# s3-pilot3.net
KiCad netlist of a schematic drawn in EAGLE
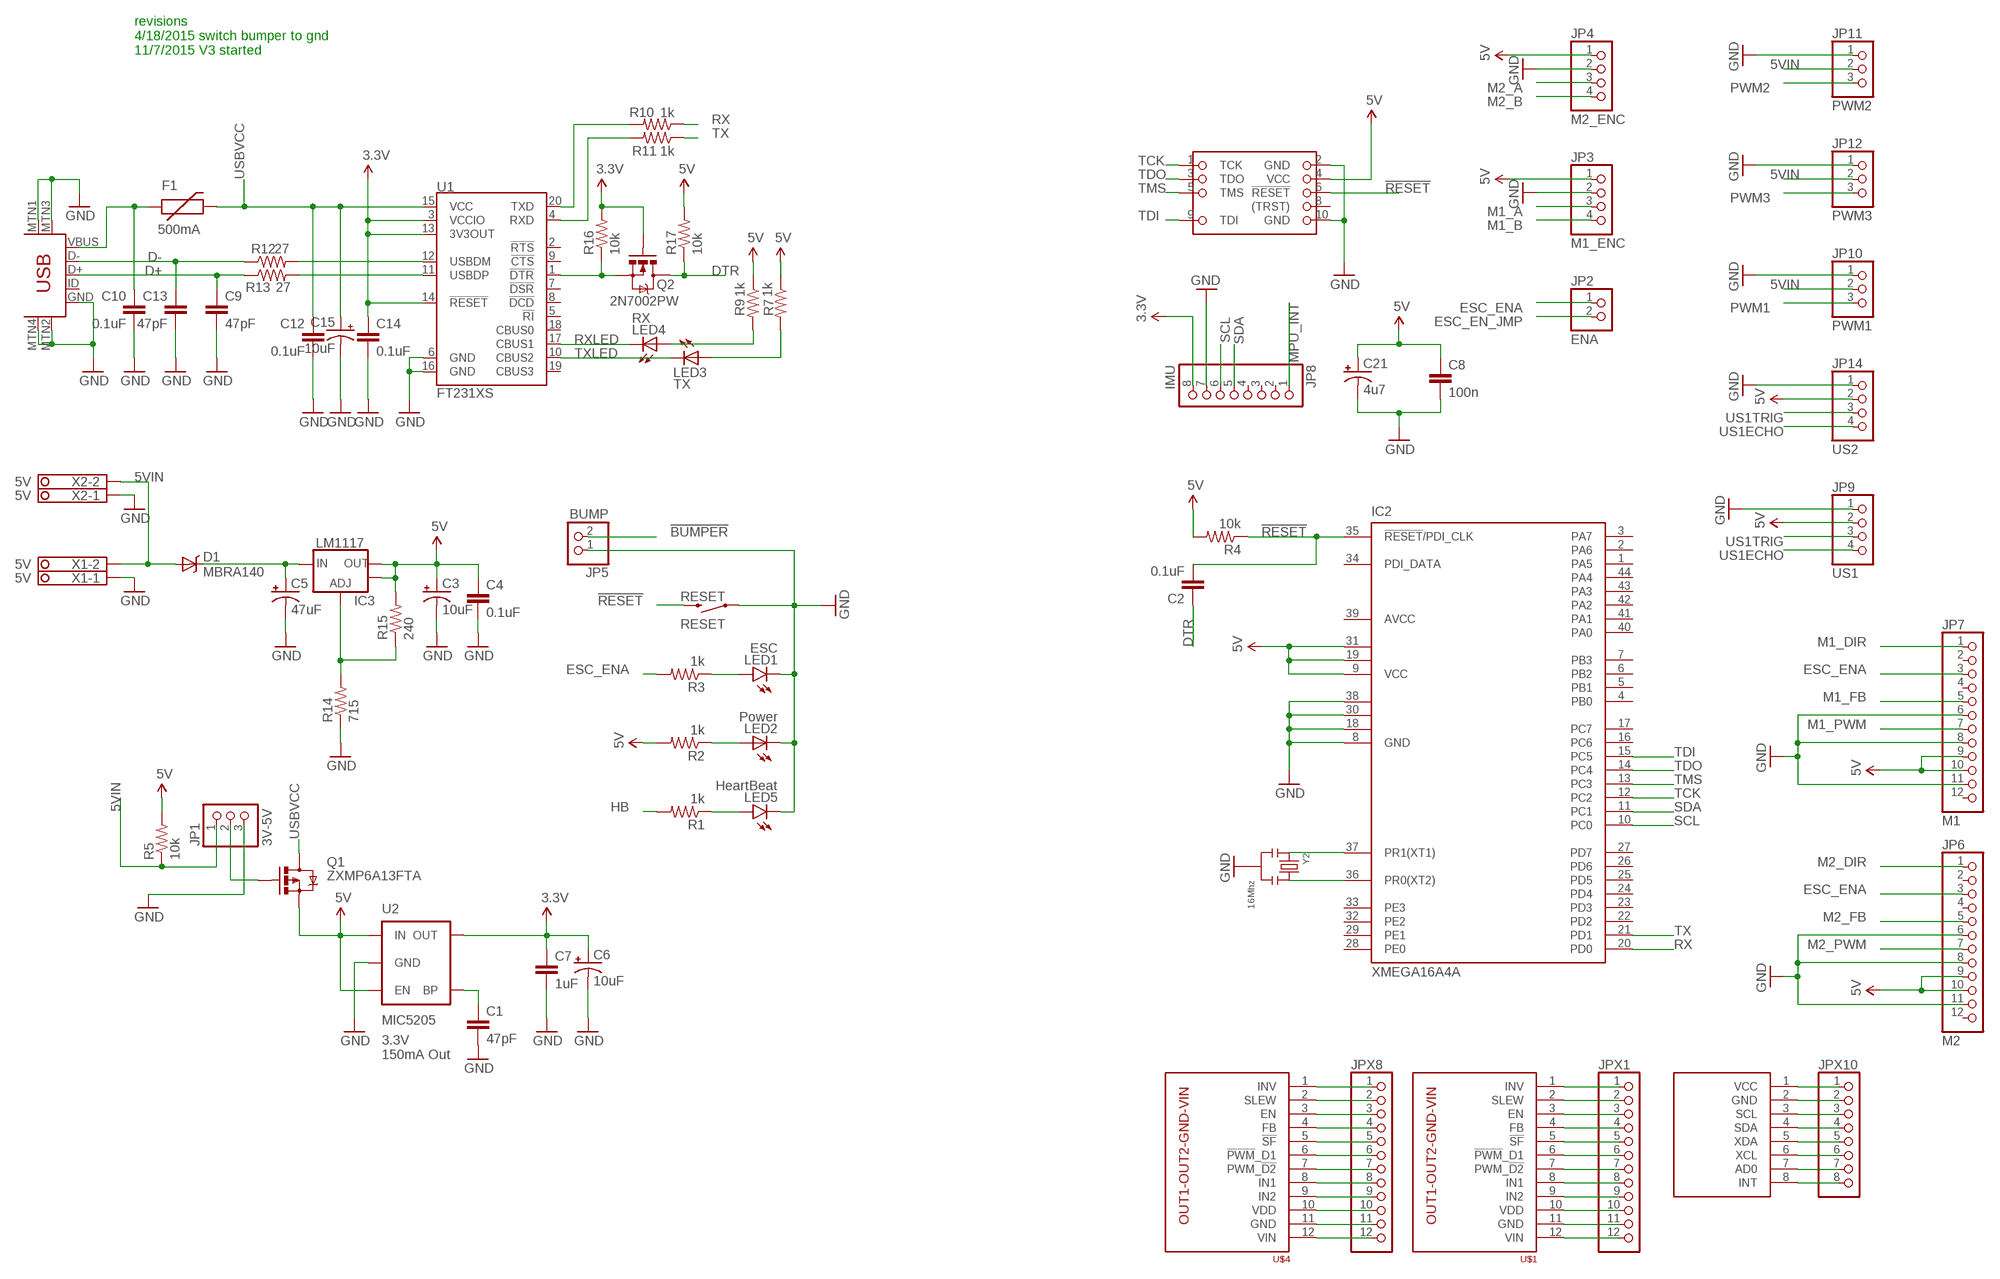
[diagram p0: schematic, sheet 1]

(export (version "E")
  (design (tool "Eeschema 10.0.6"))
  (components
    (comp (ref "C1")
      (value "47pF")
      (footprint "eagle-import:0603-CAP")
      (libsource (lib "eagle-import") (part "47PF-50V-5%(0603)"))
    )
    (comp (ref "C2")
      (value "0.1uF")
      (footprint "eagle-import:0805")
      (libsource (lib "eagle-import") (part "CAP0805"))
    )
    (comp (ref "C3")
      (value "10uF")
      (footprint "eagle-import:EIA3216")
      (libsource (lib "eagle-import") (part "CAP_POL1206"))
    )
    (comp (ref "C4")
      (value "0.1uF")
      (footprint "eagle-import:0603-CAP")
      (libsource (lib "eagle-import") (part "CAP0603-CAP"))
    )
    (comp (ref "C5")
      (value "47uF")
      (footprint "eagle-import:PANASONIC_D")
      (libsource (lib "eagle-import") (part "CAP_POLD"))
    )
    (comp (ref "C6")
      (value "10uF")
      (footprint "eagle-import:EIA3216")
      (libsource (lib "eagle-import") (part "CAP_POL1206"))
    )
    (comp (ref "C7")
      (value "1uF")
      (footprint "eagle-import:0603-CAP")
      (libsource (lib "eagle-import") (part "CAP0603-CAP"))
    )
    (comp (ref "C8")
      (value "100n")
      (footprint "eagle-import:0603-CAP")
      (libsource (lib "eagle-import") (part "CAP0603-CAP"))
    )
    (comp (ref "C9")
      (value "47pF")
      (footprint "eagle-import:0603-CAP")
      (libsource (lib "eagle-import") (part "47PF-50V-5%(0603)"))
    )
    (comp (ref "C10")
      (value "0.1uF")
      (footprint "eagle-import:0603-CAP")
      (libsource (lib "eagle-import") (part "CAP0603-CAP"))
    )
    (comp (ref "C12")
      (value "0.1uF")
      (footprint "eagle-import:0603-CAP")
      (libsource (lib "eagle-import") (part "CAP0603-CAP"))
    )
    (comp (ref "C13")
      (value "47pF")
      (footprint "eagle-import:0603-CAP")
      (libsource (lib "eagle-import") (part "47PF-50V-5%(0603)"))
    )
    (comp (ref "C14")
      (value "0.1uF")
      (footprint "eagle-import:0603-CAP")
      (libsource (lib "eagle-import") (part "CAP0603-CAP"))
    )
    (comp (ref "C15")
      (value "10uF")
      (footprint "eagle-import:EIA3216")
      (libsource (lib "eagle-import") (part "SparkFun-Capacitors_CAP_POL1206"))
    )
    (comp (ref "C21")
      (value "4u7")
      (footprint "eagle-import:EIA3216")
      (libsource (lib "eagle-import") (part "CAP_POL1206"))
    )
    (comp (ref "D1")
      (value "MBRA140")
      (footprint "eagle-import:SMA-DIODE")
      (libsource (lib "eagle-import") (part "DIODE-SCHOTTKY_"))
    )
    (comp (ref "F1")
      (value "500mA")
      (footprint "eagle-import:PTC-1206")
      (libsource (lib "eagle-import") (part "PTCSMD"))
    )
    (comp (ref "IC2")
      (value "XMEGA16A4A")
      (footprint "eagle-import:TQFP44")
      (libsource (lib "eagle-import") (part "XMEGA16A4A"))
    )
    (comp (ref "IC3")
      (value "LM1117")
      (footprint "eagle-import:SOT223")
      (libsource (lib "eagle-import") (part "V_REG_LM1117SOT223"))
    )
    (comp (ref "JP1")
      (value "3V-5V")
      (footprint "eagle-import:1X03")
      (libsource (lib "eagle-import") (part "PINHD-1X3"))
    )
    (comp (ref "JP2")
      (value "ENA")
      (footprint "eagle-import:1X02")
      (libsource (lib "eagle-import") (part "PINHD-1X2"))
    )
    (comp (ref "JP3")
      (value "M1_ENC")
      (footprint "eagle-import:1X04_90")
      (libsource (lib "eagle-import") (part "PINHD-1X4/90"))
    )
    (comp (ref "JP4")
      (value "M2_ENC")
      (footprint "eagle-import:1X04_90")
      (libsource (lib "eagle-import") (part "PINHD-1X4/90"))
    )
    (comp (ref "JP5")
      (value "BUMP")
      (footprint "eagle-import:1X02_90")
      (libsource (lib "eagle-import") (part "PINHD-1X2/90"))
    )
    (comp (ref "JP6")
      (value "M2")
      (footprint "eagle-import:1X12")
      (libsource (lib "eagle-import") (part "PINHD-1X12"))
    )
    (comp (ref "JP7")
      (value "M1")
      (footprint "eagle-import:1X12")
      (libsource (lib "eagle-import") (part "PINHD-1X12"))
    )
    (comp (ref "JP8")
      (value "IMU")
      (footprint "eagle-import:1X08")
      (libsource (lib "eagle-import") (part "PINHD-1X8"))
    )
    (comp (ref "JP9")
      (value "US1")
      (footprint "eagle-import:1X04_90")
      (libsource (lib "eagle-import") (part "PINHD-1X4/90"))
    )
    (comp (ref "JP10")
      (value "PWM1")
      (footprint "eagle-import:1X03_90")
      (libsource (lib "eagle-import") (part "PINHD-1X3/90"))
    )
    (comp (ref "JP11")
      (value "PWM2")
      (footprint "eagle-import:1X03_90")
      (libsource (lib "eagle-import") (part "PINHD-1X3/90"))
    )
    (comp (ref "JP12")
      (value "PWM3")
      (footprint "eagle-import:1X03_90")
      (libsource (lib "eagle-import") (part "PINHD-1X3/90"))
    )
    (comp (ref "JP14")
      (value "US2")
      (footprint "eagle-import:1X04_90")
      (libsource (lib "eagle-import") (part "PINHD-1X4/90"))
    )
    (comp (ref "JPX1")
      (value "PINHD-1X12")
      (footprint "eagle-import:1X12")
      (libsource (lib "eagle-import") (part "PINHD-1X12"))
    )
    (comp (ref "JPX8")
      (value "PINHD-1X12")
      (footprint "eagle-import:1X12")
      (libsource (lib "eagle-import") (part "PINHD-1X12"))
    )
    (comp (ref "JPX10")
      (value "PINHD-1X8")
      (footprint "eagle-import:1X08")
      (libsource (lib "eagle-import") (part "PINHD-1X8"))
    )
    (comp (ref "LED1")
      (value "ESC")
      (footprint "eagle-import:LED-1206")
      (libsource (lib "eagle-import") (part "LED-RED1206"))
    )
    (comp (ref "LED2")
      (value "Power")
      (footprint "eagle-import:LED-1206")
      (libsource (lib "eagle-import") (part "LED1206"))
    )
    (comp (ref "LED3")
      (value "TX")
      (footprint "eagle-import:LED-1206")
      (libsource (lib "eagle-import") (part "LED1206"))
    )
    (comp (ref "LED4")
      (value "RX")
      (footprint "eagle-import:LED-1206")
      (libsource (lib "eagle-import") (part "LED1206"))
    )
    (comp (ref "LED5")
      (value "HeartBeat")
      (footprint "eagle-import:LED-1206")
      (libsource (lib "eagle-import") (part "LED-RED1206"))
    )
    (comp (ref "MPU6050")
      (value "MPU-6050-BO")
      (footprint "eagle-import:MPU-6050-BO")
      (libsource (lib "eagle-import") (part "MPU-6050-BO"))
    )
    (comp (ref "Q1")
      (value "ZXMP6A13FTA")
      (footprint "eagle-import:SOT23-3")
      (libsource (lib "eagle-import") (part "MOSFET-PCHANNELSMD"))
    )
    (comp (ref "Q2")
      (value "2N7002PW")
      (footprint "eagle-import:SOT323")
      (libsource (lib "eagle-import") (part "MOSFET-NCHANNEL2N7002PW"))
    )
    (comp (ref "R1")
      (value "1k")
      (footprint "eagle-import:0603-RES")
      (libsource (lib "eagle-import") (part "RESISTOR0603-RES"))
    )
    (comp (ref "R2")
      (value "1k")
      (footprint "eagle-import:0603-RES")
      (libsource (lib "eagle-import") (part "RESISTOR0603-RES"))
    )
    (comp (ref "R3")
      (value "1k")
      (footprint "eagle-import:0603-RES")
      (libsource (lib "eagle-import") (part "RESISTOR0603-RES"))
    )
    (comp (ref "R4")
      (value "10k")
      (footprint "eagle-import:0603-RES")
      (libsource (lib "eagle-import") (part "RESISTOR0603-RES"))
    )
    (comp (ref "R5")
      (value "10k")
      (footprint "eagle-import:0603-RES")
      (libsource (lib "eagle-import") (part "RESISTOR0603-RES"))
    )
    (comp (ref "R7")
      (value "1k")
      (footprint "eagle-import:0603-RES")
      (libsource (lib "eagle-import") (part "RESISTOR0603-RES"))
    )
    (comp (ref "R9")
      (value "1k")
      (footprint "eagle-import:0603-RES")
      (libsource (lib "eagle-import") (part "RESISTOR0603-RES"))
    )
    (comp (ref "R10")
      (value "1k")
      (footprint "eagle-import:0603-RES")
      (libsource (lib "eagle-import") (part "RESISTOR0603-RES"))
    )
    (comp (ref "R11")
      (value "1k")
      (footprint "eagle-import:0603-RES")
      (libsource (lib "eagle-import") (part "RESISTOR0603-RES"))
    )
    (comp (ref "R12")
      (value "27")
      (footprint "eagle-import:0603-RES")
      (libsource (lib "eagle-import") (part "SparkFun-Resistors_RESISTOR0603-RES"))
    )
    (comp (ref "R13")
      (value "27")
      (footprint "eagle-import:0603-RES")
      (libsource (lib "eagle-import") (part "SparkFun-Resistors_RESISTOR0603-RES"))
    )
    (comp (ref "R14")
      (value "715")
      (footprint "eagle-import:0603-RES")
      (libsource (lib "eagle-import") (part "RESISTOR0603-RES"))
    )
    (comp (ref "R15")
      (value "240")
      (footprint "eagle-import:0603-RES")
      (libsource (lib "eagle-import") (part "RESISTOR0603-RES"))
    )
    (comp (ref "R16")
      (value "10k")
      (footprint "eagle-import:0603-RES")
      (libsource (lib "eagle-import") (part "RESISTOR0603-RES"))
    )
    (comp (ref "R17")
      (value "10k")
      (footprint "eagle-import:0603-RES")
      (libsource (lib "eagle-import") (part "RESISTOR0603-RES"))
    )
    (comp (ref "RESET")
      (value "RESET")
      (footprint "eagle-import:TACTILE_SWITCH_TALL")
      (libsource (lib "eagle-import") (part "SWITCH-MOMENTARY-2SMD-4"))
    )
    (comp (ref "U$1")
      (value "M2")
      (footprint "eagle-import:MC33926-SINGLE-BO")
      (libsource (lib "eagle-import") (part "MC33926-SINGLE-BO"))
    )
    (comp (ref "U$2")
      (value "JTAG")
      (footprint "eagle-import:2X5_05")
      (libsource (lib "eagle-import") (part "CON-JTAG"))
    )
    (comp (ref "U$4")
      (value "M2")
      (footprint "eagle-import:MC33926-SINGLE-BO")
      (libsource (lib "eagle-import") (part "MC33926-SINGLE-BO"))
    )
    (comp (ref "U$13")
      (value "USB-MINIB-5PIN")
      (footprint "eagle-import:USB-MINIB")
      (libsource (lib "eagle-import") (part "USB-MINIB-5PIN"))
    )
    (comp (ref "U1")
      (value "FT231XS")
      (footprint "eagle-import:SSOP20_L")
      (libsource (lib "eagle-import") (part "FT231XS"))
    )
    (comp (ref "U2")
      (value "MIC5205")
      (footprint "eagle-import:SOT23-5")
      (libsource (lib "eagle-import") (part "V_REG_LDOSMD"))
    )
    (comp (ref "X1")
      (value "5V")
      (footprint "eagle-import:1751248")
      (libsource (lib "eagle-import") (part "1751248"))
    )
    (comp (ref "X2")
      (value "5V")
      (footprint "eagle-import:1751248")
      (libsource (lib "eagle-import") (part "1751248"))
    )
    (comp (ref "Y2")
      (value "16Mhz")
      (footprint "eagle-import:SMD-KYOCERA-PBRV-H")
      (libsource (lib "eagle-import") (part "SMD-RESONATOR-KYOCERA-PBRV-H"))
    )
  )
  (nets
    (net (code "1") (name "/5VIN") (class "Default")
      (node (ref "D1") (pin "A") (pinfunction "A_A") (pintype "passive"))
      (node (ref "JP1") (pin "1") (pinfunction "1_1") (pintype "passive"))
      (node (ref "JP10") (pin "2") (pinfunction "2_2") (pintype "passive"))
      (node (ref "JP11") (pin "2") (pinfunction "2_2") (pintype "passive"))
      (node (ref "JP12") (pin "2") (pinfunction "2_2") (pintype "passive"))
      (node (ref "R5") (pin "1") (pinfunction "1_1") (pintype "passive"))
      (node (ref "X1") (pin "2") (pinfunction "K_2") (pintype "passive"))
      (node (ref "X2") (pin "2") (pinfunction "K_2") (pintype "passive"))
    )
    (net (code "2") (name "/AVCC") (class "Default")
      (node (ref "IC2") (pin "39") (pinfunction "AVCC_39") (pintype "power_in"))
    )
    (net (code "3") (name "/D+") (class "Default")
      (node (ref "C9") (pin "1") (pinfunction "1_1") (pintype "passive"))
      (node (ref "R13") (pin "1") (pinfunction "1_1") (pintype "passive"))
      (node (ref "U$13") (pin "D+") (pinfunction "D+_D+") (pintype "bidirectional"))
    )
    (net (code "4") (name "/D-") (class "Default")
      (node (ref "C13") (pin "1") (pinfunction "1_1") (pintype "passive"))
      (node (ref "R12") (pin "1") (pinfunction "1_1") (pintype "passive"))
      (node (ref "U$13") (pin "D-") (pinfunction "D-_D-") (pintype "bidirectional"))
    )
    (net (code "5") (name "/DTR") (class "Default")
      (node (ref "C2") (pin "1") (pinfunction "1_1") (pintype "passive"))
      (node (ref "Q2") (pin "3") (pinfunction "D_3") (pintype "passive"))
      (node (ref "R17") (pin "1") (pinfunction "1_1") (pintype "passive"))
    )
    (net (code "6") (name "/ESC_ENA") (class "Default")
      (node (ref "JP2") (pin "1") (pinfunction "1_1") (pintype "passive"))
      (node (ref "JP6") (pin "3") (pinfunction "3_3") (pintype "passive"))
      (node (ref "JP7") (pin "3") (pinfunction "3_3") (pintype "passive"))
      (node (ref "R3") (pin "2") (pinfunction "2_2") (pintype "passive"))
    )
    (net (code "7") (name "/ESC_EN_JMP") (class "Default")
      (node (ref "JP2") (pin "2") (pinfunction "2_2") (pintype "passive"))
    )
    (net (code "8") (name "/HB") (class "Default")
      (node (ref "R1") (pin "2") (pinfunction "2_2") (pintype "passive"))
    )
    (net (code "9") (name "/M1_A") (class "Default")
      (node (ref "JP3") (pin "3") (pinfunction "3_3") (pintype "passive"))
    )
    (net (code "10") (name "/M1_B") (class "Default")
      (node (ref "JP3") (pin "4") (pinfunction "4_4") (pintype "passive"))
    )
    (net (code "11") (name "/M1_DIR") (class "Default")
      (node (ref "JP7") (pin "1") (pinfunction "1_1") (pintype "passive"))
    )
    (net (code "12") (name "/M1_FB") (class "Default")
      (node (ref "JP7") (pin "5") (pinfunction "5_5") (pintype "passive"))
    )
    (net (code "13") (name "/M1_PWM") (class "Default")
      (node (ref "JP7") (pin "7") (pinfunction "7_7") (pintype "passive"))
    )
    (net (code "14") (name "/M2_A") (class "Default")
      (node (ref "JP4") (pin "3") (pinfunction "3_3") (pintype "passive"))
    )
    (net (code "15") (name "/M2_B") (class "Default")
      (node (ref "JP4") (pin "4") (pinfunction "4_4") (pintype "passive"))
    )
    (net (code "16") (name "/M2_DIR") (class "Default")
      (node (ref "JP6") (pin "1") (pinfunction "1_1") (pintype "passive"))
    )
    (net (code "17") (name "/M2_FB") (class "Default")
      (node (ref "JP6") (pin "5") (pinfunction "5_5") (pintype "passive"))
    )
    (net (code "18") (name "/M2_PWM") (class "Default")
      (node (ref "JP6") (pin "7") (pinfunction "7_7") (pintype "passive"))
    )
    (net (code "19") (name "/MPU_INT") (class "Default")
      (node (ref "JP8") (pin "1") (pinfunction "1_1") (pintype "passive"))
    )
    (net (code "20") (name "/PWM1") (class "Default")
      (node (ref "JP10") (pin "3") (pinfunction "3_3") (pintype "passive"))
    )
    (net (code "21") (name "/PWM2") (class "Default")
      (node (ref "JP11") (pin "3") (pinfunction "3_3") (pintype "passive"))
    )
    (net (code "22") (name "/PWM3") (class "Default")
      (node (ref "JP12") (pin "3") (pinfunction "3_3") (pintype "passive"))
    )
    (net (code "23") (name "/RX") (class "Default")
      (node (ref "IC2") (pin "20") (pinfunction "PD0_20") (pintype "bidirectional"))
      (node (ref "R10") (pin "1") (pinfunction "1_1") (pintype "passive"))
    )
    (net (code "24") (name "/RXLED") (class "Default")
      (node (ref "LED4") (pin "C") (pinfunction "C_C") (pintype "passive"))
      (node (ref "U1") (pin "17") (pinfunction "CBUS1_17") (pintype "bidirectional"))
    )
    (net (code "25") (name "/SCL") (class "Default")
      (node (ref "IC2") (pin "10") (pinfunction "PC0_10") (pintype "bidirectional"))
      (node (ref "JP8") (pin "6") (pinfunction "6_6") (pintype "passive"))
    )
    (net (code "26") (name "/SDA") (class "Default")
      (node (ref "IC2") (pin "11") (pinfunction "PC1_11") (pintype "bidirectional"))
      (node (ref "JP8") (pin "5") (pinfunction "5_5") (pintype "passive"))
    )
    (net (code "27") (name "/TCK") (class "Default")
      (node (ref "IC2") (pin "12") (pinfunction "PC2_12") (pintype "bidirectional"))
      (node (ref "U$2") (pin "1") (pinfunction "TCK_1") (pintype "bidirectional"))
    )
    (net (code "28") (name "/TDI") (class "Default")
      (node (ref "IC2") (pin "15") (pinfunction "PC5_15") (pintype "bidirectional"))
      (node (ref "U$2") (pin "9") (pinfunction "TDI_9") (pintype "bidirectional"))
    )
    (net (code "29") (name "/TDO") (class "Default")
      (node (ref "IC2") (pin "14") (pinfunction "PC4_14") (pintype "bidirectional"))
      (node (ref "U$2") (pin "3") (pinfunction "TDO_3") (pintype "bidirectional"))
    )
    (net (code "30") (name "/TMS") (class "Default")
      (node (ref "IC2") (pin "13") (pinfunction "PC3_13") (pintype "bidirectional"))
      (node (ref "U$2") (pin "5") (pinfunction "TMS_5") (pintype "bidirectional"))
    )
    (net (code "31") (name "/TX") (class "Default")
      (node (ref "IC2") (pin "21") (pinfunction "PD1_21") (pintype "bidirectional"))
      (node (ref "R11") (pin "1") (pinfunction "1_1") (pintype "passive"))
    )
    (net (code "32") (name "/TXLED") (class "Default")
      (node (ref "LED3") (pin "C") (pinfunction "C_C") (pintype "passive"))
      (node (ref "U1") (pin "10") (pinfunction "CBUS2_10") (pintype "bidirectional"))
    )
    (net (code "33") (name "/US1ECHO") (class "Default")
      (node (ref "JP14") (pin "4") (pinfunction "4_4") (pintype "passive"))
      (node (ref "JP9") (pin "4") (pinfunction "4_4") (pintype "passive"))
    )
    (net (code "34") (name "/US1TRIG") (class "Default")
      (node (ref "JP14") (pin "3") (pinfunction "3_3") (pintype "passive"))
      (node (ref "JP9") (pin "3") (pinfunction "3_3") (pintype "passive"))
    )
    (net (code "35") (name "/USBVCC") (class "Default")
      (node (ref "C12") (pin "1") (pinfunction "1_1") (pintype "passive"))
      (node (ref "C15") (pin "A") (pinfunction "+_A") (pintype "passive"))
      (node (ref "F1") (pin "2") (pinfunction "2_2") (pintype "bidirectional"))
      (node (ref "Q1") (pin "3") (pinfunction "D_3") (pintype "passive"))
      (node (ref "U1") (pin "15") (pinfunction "VCC_15") (pintype "bidirectional"))
    )
    (net (code "36") (name "/~{BUMPER}") (class "Default")
      (node (ref "JP5") (pin "2") (pinfunction "2_2") (pintype "passive"))
    )
    (net (code "37") (name "/~{RESET}") (class "Default")
      (node (ref "C2") (pin "2") (pinfunction "2_2") (pintype "passive"))
      (node (ref "IC2") (pin "35") (pinfunction "~{RESET}/PDI_CLK_35") (pintype "bidirectional"))
      (node (ref "R4") (pin "1") (pinfunction "1_1") (pintype "passive"))
      (node (ref "RESET") (pin "B2") (pinfunction "2_B2") (pintype "passive"))
      (node (ref "U$2") (pin "6") (pinfunction "~{RESET}_6") (pintype "bidirectional"))
    )
    (net (code "38") (name "3.3V") (class "Default")
      (node (ref "C14") (pin "1") (pinfunction "1_1") (pintype "passive"))
      (node (ref "C6") (pin "A") (pinfunction "+_A") (pintype "passive"))
      (node (ref "C7") (pin "1") (pinfunction "1_1") (pintype "passive"))
      (node (ref "JP8") (pin "8") (pinfunction "8_8") (pintype "passive"))
      (node (ref "Q2") (pin "1") (pinfunction "G_1") (pintype "passive"))
      (node (ref "R16") (pin "2") (pinfunction "2_2") (pintype "passive"))
      (node (ref "U1") (pin "13") (pinfunction "3V3OUT_13") (pintype "bidirectional"))
      (node (ref "U1") (pin "14") (pinfunction "~{RESET}_14") (pintype "bidirectional"))
      (node (ref "U1") (pin "3") (pinfunction "VCCIO_3") (pintype "bidirectional"))
      (node (ref "U2") (pin "5") (pinfunction "OUT_5") (pintype "passive"))
    )
    (net (code "39") (name "5V") (class "Default")
      (node (ref "C21") (pin "A") (pinfunction "+_A") (pintype "passive"))
      (node (ref "C3") (pin "A") (pinfunction "+_A") (pintype "passive"))
      (node (ref "C4") (pin "1") (pinfunction "1_1") (pintype "passive"))
      (node (ref "C8") (pin "1") (pinfunction "1_1") (pintype "passive"))
      (node (ref "IC2") (pin "19") (pinfunction "VCC1_19") (pintype "power_in"))
      (node (ref "IC2") (pin "31") (pinfunction "VCC2_31") (pintype "power_in"))
      (node (ref "IC2") (pin "9") (pinfunction "VCC_9") (pintype "power_in"))
      (node (ref "IC3") (pin "2") (pinfunction "OUT_2") (pintype "output"))
      (node (ref "IC3") (pin "4") (pinfunction "OUT_4") (pintype "output"))
      (node (ref "JP14") (pin "2") (pinfunction "2_2") (pintype "passive"))
      (node (ref "JP3") (pin "1") (pinfunction "1_1") (pintype "passive"))
      (node (ref "JP4") (pin "1") (pinfunction "1_1") (pintype "passive"))
      (node (ref "JP6") (pin "10") (pinfunction "10_10") (pintype "passive"))
      (node (ref "JP6") (pin "9") (pinfunction "9_9") (pintype "passive"))
      (node (ref "JP7") (pin "10") (pinfunction "10_10") (pintype "passive"))
      (node (ref "JP7") (pin "9") (pinfunction "9_9") (pintype "passive"))
      (node (ref "JP9") (pin "2") (pinfunction "2_2") (pintype "passive"))
      (node (ref "Q1") (pin "2") (pinfunction "S_2") (pintype "passive"))
      (node (ref "R15") (pin "2") (pinfunction "2_2") (pintype "passive"))
      (node (ref "R17") (pin "2") (pinfunction "2_2") (pintype "passive"))
      (node (ref "R2") (pin "2") (pinfunction "2_2") (pintype "passive"))
      (node (ref "R4") (pin "2") (pinfunction "2_2") (pintype "passive"))
      (node (ref "R5") (pin "2") (pinfunction "2_2") (pintype "passive"))
      (node (ref "R7") (pin "1") (pinfunction "1_1") (pintype "passive"))
      (node (ref "R9") (pin "1") (pinfunction "1_1") (pintype "passive"))
      (node (ref "U$2") (pin "4") (pinfunction "VCC_4") (pintype "power_in"))
      (node (ref "U2") (pin "1") (pinfunction "IN_1") (pintype "input"))
      (node (ref "U2") (pin "3") (pinfunction "EN_3") (pintype "input"))
    )
    (net (code "40") (name "GND") (class "Default")
      (node (ref "C1") (pin "2") (pinfunction "2_2") (pintype "passive"))
      (node (ref "C10") (pin "2") (pinfunction "2_2") (pintype "passive"))
      (node (ref "C12") (pin "2") (pinfunction "2_2") (pintype "passive"))
      (node (ref "C13") (pin "2") (pinfunction "2_2") (pintype "passive"))
      (node (ref "C14") (pin "2") (pinfunction "2_2") (pintype "passive"))
      (node (ref "C15") (pin "C") (pinfunction "-_C") (pintype "passive"))
      (node (ref "C21") (pin "C") (pinfunction "-_C") (pintype "passive"))
      (node (ref "C3") (pin "C") (pinfunction "-_C") (pintype "passive"))
      (node (ref "C4") (pin "2") (pinfunction "2_2") (pintype "passive"))
      (node (ref "C5") (pin "-") (pinfunction "-_-") (pintype "passive"))
      (node (ref "C6") (pin "C") (pinfunction "-_C") (pintype "passive"))
      (node (ref "C7") (pin "2") (pinfunction "2_2") (pintype "passive"))
      (node (ref "C8") (pin "2") (pinfunction "2_2") (pintype "passive"))
      (node (ref "C9") (pin "2") (pinfunction "2_2") (pintype "passive"))
      (node (ref "IC2") (pin "18") (pinfunction "GND1_18") (pintype "power_in"))
      (node (ref "IC2") (pin "30") (pinfunction "GND2_30") (pintype "power_in"))
      (node (ref "IC2") (pin "38") (pinfunction "GND3_38") (pintype "power_in"))
      (node (ref "IC2") (pin "8") (pinfunction "GND_8") (pintype "power_in"))
      (node (ref "JP1") (pin "3") (pinfunction "3_3") (pintype "passive"))
      (node (ref "JP10") (pin "1") (pinfunction "1_1") (pintype "passive"))
      (node (ref "JP11") (pin "1") (pinfunction "1_1") (pintype "passive"))
      (node (ref "JP12") (pin "1") (pinfunction "1_1") (pintype "passive"))
      (node (ref "JP14") (pin "1") (pinfunction "1_1") (pintype "passive"))
      (node (ref "JP3") (pin "2") (pinfunction "2_2") (pintype "passive"))
      (node (ref "JP4") (pin "2") (pinfunction "2_2") (pintype "passive"))
      (node (ref "JP5") (pin "1") (pinfunction "1_1") (pintype "passive"))
      (node (ref "JP6") (pin "11") (pinfunction "11_11") (pintype "passive"))
      (node (ref "JP6") (pin "6") (pinfunction "6_6") (pintype "passive"))
      (node (ref "JP6") (pin "8") (pinfunction "8_8") (pintype "passive"))
      (node (ref "JP7") (pin "11") (pinfunction "11_11") (pintype "passive"))
      (node (ref "JP7") (pin "6") (pinfunction "6_6") (pintype "passive"))
      (node (ref "JP7") (pin "8") (pinfunction "8_8") (pintype "passive"))
      (node (ref "JP8") (pin "7") (pinfunction "7_7") (pintype "passive"))
      (node (ref "JP9") (pin "1") (pinfunction "1_1") (pintype "passive"))
      (node (ref "LED1") (pin "C") (pinfunction "C_C") (pintype "passive"))
      (node (ref "LED2") (pin "C") (pinfunction "C_C") (pintype "passive"))
      (node (ref "LED5") (pin "C") (pinfunction "C_C") (pintype "passive"))
      (node (ref "R14") (pin "1") (pinfunction "1_1") (pintype "passive"))
      (node (ref "RESET") (pin "A2") (pinfunction "1_A2") (pintype "passive"))
      (node (ref "U$13") (pin "GND") (pinfunction "GND_GND") (pintype "bidirectional"))
      (node (ref "U$13") (pin "MTN1") (pinfunction "MTN2_MTN1") (pintype "bidirectional"))
      (node (ref "U$13") (pin "MTN2") (pinfunction "MTN3_MTN2") (pintype "bidirectional"))
      (node (ref "U$13") (pin "MTN3") (pinfunction "MTN1_MTN3") (pintype "bidirectional"))
      (node (ref "U$13") (pin "MTN4") (pinfunction "MTN4_MTN4") (pintype "bidirectional"))
      (node (ref "U$2") (pin "10") (pinfunction "GND_10") (pintype "power_in"))
      (node (ref "U$2") (pin "2") (pinfunction "GND_2") (pintype "power_in"))
      (node (ref "U1") (pin "16") (pinfunction "GND_16") (pintype "bidirectional"))
      (node (ref "U1") (pin "6") (pinfunction "GND_6") (pintype "bidirectional"))
      (node (ref "U2") (pin "2") (pinfunction "GND_2") (pintype "input"))
      (node (ref "X1") (pin "1") (pinfunction "K_1") (pintype "passive"))
      (node (ref "X2") (pin "1") (pinfunction "K_1") (pintype "passive"))
      (node (ref "Y2") (pin "2") (pinfunction "2_2") (pintype "passive"))
    )
    (net (code "41") (name "Net-(C10-Pad1)") (class "Default")
      (node (ref "C10") (pin "1") (pinfunction "1_1") (pintype "passive"))
      (node (ref "F1") (pin "1") (pinfunction "1_1") (pintype "bidirectional"))
      (node (ref "U$13") (pin "VBUS") (pinfunction "VBUS_VBUS") (pintype "bidirectional"))
    )
    (net (code "42") (name "Net-(IC2-PR0(XT2))") (class "Default")
      (node (ref "IC2") (pin "36") (pinfunction "PR0(XT2)_36") (pintype "bidirectional"))
      (node (ref "Y2") (pin "3") (pinfunction "3_3") (pintype "passive"))
    )
    (net (code "43") (name "Net-(IC2-PR1(XT1))") (class "Default")
      (node (ref "IC2") (pin "37") (pinfunction "PR1(XT1)_37") (pintype "bidirectional"))
      (node (ref "Y2") (pin "1") (pinfunction "1_1") (pintype "passive"))
    )
    (net (code "44") (name "Net-(IC3-ADJ)") (class "Default")
      (node (ref "IC3") (pin "1") (pinfunction "ADJ_1") (pintype "input"))
      (node (ref "R14") (pin "2") (pinfunction "2_2") (pintype "passive"))
      (node (ref "R15") (pin "1") (pinfunction "1_1") (pintype "passive"))
    )
    (net (code "45") (name "Net-(IC3-IN)") (class "Default")
      (node (ref "C5") (pin "+") (pinfunction "+_+") (pintype "passive"))
      (node (ref "D1") (pin "C") (pinfunction "C_C") (pintype "passive"))
      (node (ref "IC3") (pin "3") (pinfunction "IN_3") (pintype "input"))
    )
    (net (code "46") (name "Net-(LED1-PadA)") (class "Default")
      (node (ref "LED1") (pin "A") (pinfunction "A_A") (pintype "passive"))
      (node (ref "R3") (pin "1") (pinfunction "1_1") (pintype "passive"))
    )
    (net (code "47") (name "Net-(LED2-PadA)") (class "Default")
      (node (ref "LED2") (pin "A") (pinfunction "A_A") (pintype "passive"))
      (node (ref "R2") (pin "1") (pinfunction "1_1") (pintype "passive"))
    )
    (net (code "48") (name "Net-(LED3-PadA)") (class "Default")
      (node (ref "LED3") (pin "A") (pinfunction "A_A") (pintype "passive"))
      (node (ref "R7") (pin "2") (pinfunction "2_2") (pintype "passive"))
    )
    (net (code "49") (name "Net-(LED4-PadA)") (class "Default")
      (node (ref "LED4") (pin "A") (pinfunction "A_A") (pintype "passive"))
      (node (ref "R9") (pin "2") (pinfunction "2_2") (pintype "passive"))
    )
    (net (code "50") (name "Net-(LED5-PadA)") (class "Default")
      (node (ref "LED5") (pin "A") (pinfunction "A_A") (pintype "passive"))
      (node (ref "R1") (pin "1") (pinfunction "1_1") (pintype "passive"))
    )
    (net (code "51") (name "Net-(MPU6050-AD0)") (class "Default")
      (node (ref "JPX10") (pin "7") (pinfunction "7_7") (pintype "passive"))
      (node (ref "MPU6050") (pin "7") (pinfunction "AD0_7") (pintype "input"))
    )
    (net (code "52") (name "Net-(MPU6050-GND)") (class "Default")
      (node (ref "JPX10") (pin "2") (pinfunction "2_2") (pintype "passive"))
      (node (ref "MPU6050") (pin "2") (pinfunction "GND_2") (pintype "power_in"))
    )
    (net (code "53") (name "Net-(MPU6050-INT)") (class "Default")
      (node (ref "JPX10") (pin "8") (pinfunction "8_8") (pintype "passive"))
      (node (ref "MPU6050") (pin "8") (pinfunction "INT_8") (pintype "output"))
    )
    (net (code "54") (name "Net-(MPU6050-SCL)") (class "Default")
      (node (ref "JPX10") (pin "3") (pinfunction "3_3") (pintype "passive"))
      (node (ref "MPU6050") (pin "3") (pinfunction "SCL_3") (pintype "bidirectional"))
    )
    (net (code "55") (name "Net-(MPU6050-SDA)") (class "Default")
      (node (ref "JPX10") (pin "4") (pinfunction "4_4") (pintype "passive"))
      (node (ref "MPU6050") (pin "4") (pinfunction "SDA_4") (pintype "bidirectional"))
    )
    (net (code "56") (name "Net-(MPU6050-VCC)") (class "Default")
      (node (ref "JPX10") (pin "1") (pinfunction "1_1") (pintype "passive"))
      (node (ref "MPU6050") (pin "1") (pinfunction "VCC_1") (pintype "power_in"))
    )
    (net (code "57") (name "Net-(MPU6050-XCL)") (class "Default")
      (node (ref "JPX10") (pin "6") (pinfunction "6_6") (pintype "passive"))
      (node (ref "MPU6050") (pin "6") (pinfunction "XCL_6") (pintype "bidirectional"))
    )
    (net (code "58") (name "Net-(MPU6050-XDA)") (class "Default")
      (node (ref "JPX10") (pin "5") (pinfunction "5_5") (pintype "passive"))
      (node (ref "MPU6050") (pin "5") (pinfunction "XDA_5") (pintype "bidirectional"))
    )
    (net (code "59") (name "Net-(Q1-G)") (class "Default")
      (node (ref "JP1") (pin "2") (pinfunction "2_2") (pintype "passive"))
      (node (ref "Q1") (pin "1") (pinfunction "G_1") (pintype "passive"))
    )
    (net (code "60") (name "Net-(Q2-S)") (class "Default")
      (node (ref "Q2") (pin "2") (pinfunction "S_2") (pintype "passive"))
      (node (ref "R16") (pin "1") (pinfunction "1_1") (pintype "passive"))
      (node (ref "U1") (pin "1") (pinfunction "~{DTR}_1") (pintype "bidirectional"))
    )
    (net (code "61") (name "Net-(U$1-EN)") (class "Default")
      (node (ref "JPX1") (pin "3") (pinfunction "3_3") (pintype "passive"))
      (node (ref "U$1") (pin "3") (pinfunction "EN_3") (pintype "input"))
    )
    (net (code "62") (name "Net-(U$1-FB)") (class "Default")
      (node (ref "JPX1") (pin "4") (pinfunction "4_4") (pintype "passive"))
      (node (ref "U$1") (pin "4") (pinfunction "FB_4") (pintype "output"))
    )
    (net (code "63") (name "Net-(U$1-GND)") (class "Default")
      (node (ref "JPX1") (pin "11") (pinfunction "11_11") (pintype "passive"))
      (node (ref "U$1") (pin "11") (pinfunction "GND_11") (pintype "power_in"))
    )
    (net (code "64") (name "Net-(U$1-IN1)") (class "Default")
      (node (ref "JPX1") (pin "8") (pinfunction "8_8") (pintype "passive"))
      (node (ref "U$1") (pin "8") (pinfunction "IN1_8") (pintype "input"))
    )
    (net (code "65") (name "Net-(U$1-IN2)") (class "Default")
      (node (ref "JPX1") (pin "9") (pinfunction "9_9") (pintype "passive"))
      (node (ref "U$1") (pin "9") (pinfunction "IN2_9") (pintype "input"))
    )
    (net (code "66") (name "Net-(U$1-INV)") (class "Default")
      (node (ref "JPX1") (pin "1") (pinfunction "1_1") (pintype "passive"))
      (node (ref "U$1") (pin "1") (pinfunction "INV_1") (pintype "input"))
    )
    (net (code "67") (name "Net-(U$1-PWM_~{D2})") (class "Default")
      (node (ref "JPX1") (pin "7") (pinfunction "7_7") (pintype "passive"))
      (node (ref "U$1") (pin "7") (pinfunction "PWM_~{D2}_7") (pintype "input"))
    )
    (net (code "68") (name "Net-(U$1-SLEW)") (class "Default")
      (node (ref "JPX1") (pin "2") (pinfunction "2_2") (pintype "passive"))
      (node (ref "U$1") (pin "2") (pinfunction "SLEW_2") (pintype "input"))
    )
    (net (code "69") (name "Net-(U$1-VDD)") (class "Default")
      (node (ref "JPX1") (pin "10") (pinfunction "10_10") (pintype "passive"))
      (node (ref "U$1") (pin "10") (pinfunction "VDD_10") (pintype "power_in"))
    )
    (net (code "70") (name "Net-(U$1-VIN)") (class "Default")
      (node (ref "JPX1") (pin "12") (pinfunction "12_12") (pintype "passive"))
      (node (ref "U$1") (pin "12") (pinfunction "VIN_12") (pintype "power_in"))
    )
    (net (code "71") (name "Net-(U$1-~{PWM}_D1)") (class "Default")
      (node (ref "JPX1") (pin "6") (pinfunction "6_6") (pintype "passive"))
      (node (ref "U$1") (pin "6") (pinfunction "~{PWM}_D1_6") (pintype "input"))
    )
    (net (code "72") (name "Net-(U$1-~{SF})") (class "Default")
      (node (ref "JPX1") (pin "5") (pinfunction "5_5") (pintype "passive"))
      (node (ref "U$1") (pin "5") (pinfunction "~{SF}_5") (pintype "output"))
    )
    (net (code "73") (name "Net-(U$4-EN)") (class "Default")
      (node (ref "JPX8") (pin "3") (pinfunction "3_3") (pintype "passive"))
      (node (ref "U$4") (pin "3") (pinfunction "EN_3") (pintype "input"))
    )
    (net (code "74") (name "Net-(U$4-FB)") (class "Default")
      (node (ref "JPX8") (pin "4") (pinfunction "4_4") (pintype "passive"))
      (node (ref "U$4") (pin "4") (pinfunction "FB_4") (pintype "output"))
    )
    (net (code "75") (name "Net-(U$4-GND)") (class "Default")
      (node (ref "JPX8") (pin "11") (pinfunction "11_11") (pintype "passive"))
      (node (ref "U$4") (pin "11") (pinfunction "GND_11") (pintype "power_in"))
    )
    (net (code "76") (name "Net-(U$4-IN1)") (class "Default")
      (node (ref "JPX8") (pin "8") (pinfunction "8_8") (pintype "passive"))
      (node (ref "U$4") (pin "8") (pinfunction "IN1_8") (pintype "input"))
    )
    (net (code "77") (name "Net-(U$4-IN2)") (class "Default")
      (node (ref "JPX8") (pin "9") (pinfunction "9_9") (pintype "passive"))
      (node (ref "U$4") (pin "9") (pinfunction "IN2_9") (pintype "input"))
    )
    (net (code "78") (name "Net-(U$4-INV)") (class "Default")
      (node (ref "JPX8") (pin "1") (pinfunction "1_1") (pintype "passive"))
      (node (ref "U$4") (pin "1") (pinfunction "INV_1") (pintype "input"))
    )
    (net (code "79") (name "Net-(U$4-PWM_~{D2})") (class "Default")
      (node (ref "JPX8") (pin "7") (pinfunction "7_7") (pintype "passive"))
      (node (ref "U$4") (pin "7") (pinfunction "PWM_~{D2}_7") (pintype "input"))
    )
    (net (code "80") (name "Net-(U$4-SLEW)") (class "Default")
      (node (ref "JPX8") (pin "2") (pinfunction "2_2") (pintype "passive"))
      (node (ref "U$4") (pin "2") (pinfunction "SLEW_2") (pintype "input"))
    )
    (net (code "81") (name "Net-(U$4-VDD)") (class "Default")
      (node (ref "JPX8") (pin "10") (pinfunction "10_10") (pintype "passive"))
      (node (ref "U$4") (pin "10") (pinfunction "VDD_10") (pintype "power_in"))
    )
    (net (code "82") (name "Net-(U$4-VIN)") (class "Default")
      (node (ref "JPX8") (pin "12") (pinfunction "12_12") (pintype "passive"))
      (node (ref "U$4") (pin "12") (pinfunction "VIN_12") (pintype "power_in"))
    )
    (net (code "83") (name "Net-(U$4-~{PWM}_D1)") (class "Default")
      (node (ref "JPX8") (pin "6") (pinfunction "6_6") (pintype "passive"))
      (node (ref "U$4") (pin "6") (pinfunction "~{PWM}_D1_6") (pintype "input"))
    )
    (net (code "84") (name "Net-(U$4-~{SF})") (class "Default")
      (node (ref "JPX8") (pin "5") (pinfunction "5_5") (pintype "passive"))
      (node (ref "U$4") (pin "5") (pinfunction "~{SF}_5") (pintype "output"))
    )
    (net (code "85") (name "Net-(U1-RXD)") (class "Default")
      (node (ref "R11") (pin "2") (pinfunction "2_2") (pintype "passive"))
      (node (ref "U1") (pin "4") (pinfunction "RXD_4") (pintype "bidirectional"))
    )
    (net (code "86") (name "Net-(U1-TXD)") (class "Default")
      (node (ref "R10") (pin "2") (pinfunction "2_2") (pintype "passive"))
      (node (ref "U1") (pin "20") (pinfunction "TXD_20") (pintype "bidirectional"))
    )
    (net (code "87") (name "Net-(U1-USBDM)") (class "Default")
      (node (ref "R12") (pin "2") (pinfunction "2_2") (pintype "passive"))
      (node (ref "U1") (pin "12") (pinfunction "USBDM_12") (pintype "bidirectional"))
    )
    (net (code "88") (name "Net-(U1-USBDP)") (class "Default")
      (node (ref "R13") (pin "2") (pinfunction "2_2") (pintype "passive"))
      (node (ref "U1") (pin "11") (pinfunction "USBDP_11") (pintype "bidirectional"))
    )
    (net (code "89") (name "Net-(U2-BP)") (class "Default")
      (node (ref "C1") (pin "1") (pinfunction "1_1") (pintype "passive"))
      (node (ref "U2") (pin "4") (pinfunction "BP_4") (pintype "input"))
    )
    (net (code "90") (name "unconnected-(IC2-PA0-Pad40)") (class "Default")
      (node (ref "IC2") (pin "40") (pinfunction "PA0_40") (pintype "bidirectional"))
    )
    (net (code "91") (name "unconnected-(IC2-PA1-Pad41)") (class "Default")
      (node (ref "IC2") (pin "41") (pinfunction "PA1_41") (pintype "bidirectional"))
    )
    (net (code "92") (name "unconnected-(IC2-PA2-Pad42)") (class "Default")
      (node (ref "IC2") (pin "42") (pinfunction "PA2_42") (pintype "bidirectional"))
    )
    (net (code "93") (name "unconnected-(IC2-PA3-Pad43)") (class "Default")
      (node (ref "IC2") (pin "43") (pinfunction "PA3_43") (pintype "bidirectional"))
    )
    (net (code "94") (name "unconnected-(IC2-PA4-Pad44)") (class "Default")
      (node (ref "IC2") (pin "44") (pinfunction "PA4_44") (pintype "bidirectional"))
    )
    (net (code "95") (name "unconnected-(IC2-PA5-Pad1)") (class "Default")
      (node (ref "IC2") (pin "1") (pinfunction "PA5_1") (pintype "bidirectional"))
    )
    (net (code "96") (name "unconnected-(IC2-PA6-Pad2)") (class "Default")
      (node (ref "IC2") (pin "2") (pinfunction "PA6_2") (pintype "bidirectional"))
    )
    (net (code "97") (name "unconnected-(IC2-PA7-Pad3)") (class "Default")
      (node (ref "IC2") (pin "3") (pinfunction "PA7_3") (pintype "bidirectional"))
    )
    (net (code "98") (name "unconnected-(IC2-PB0-Pad4)") (class "Default")
      (node (ref "IC2") (pin "4") (pinfunction "PB0_4") (pintype "bidirectional"))
    )
    (net (code "99") (name "unconnected-(IC2-PB1-Pad5)") (class "Default")
      (node (ref "IC2") (pin "5") (pinfunction "PB1_5") (pintype "bidirectional"))
    )
    (net (code "100") (name "unconnected-(IC2-PB2-Pad6)") (class "Default")
      (node (ref "IC2") (pin "6") (pinfunction "PB2_6") (pintype "bidirectional"))
    )
    (net (code "101") (name "unconnected-(IC2-PB3-Pad7)") (class "Default")
      (node (ref "IC2") (pin "7") (pinfunction "PB3_7") (pintype "bidirectional"))
    )
    (net (code "102") (name "unconnected-(IC2-PC6-Pad16)") (class "Default")
      (node (ref "IC2") (pin "16") (pinfunction "PC6_16") (pintype "bidirectional"))
    )
    (net (code "103") (name "unconnected-(IC2-PC7-Pad17)") (class "Default")
      (node (ref "IC2") (pin "17") (pinfunction "PC7_17") (pintype "bidirectional"))
    )
    (net (code "104") (name "unconnected-(IC2-PD2-Pad22)") (class "Default")
      (node (ref "IC2") (pin "22") (pinfunction "PD2_22") (pintype "bidirectional"))
    )
    (net (code "105") (name "unconnected-(IC2-PD3-Pad23)") (class "Default")
      (node (ref "IC2") (pin "23") (pinfunction "PD3_23") (pintype "bidirectional"))
    )
    (net (code "106") (name "unconnected-(IC2-PD4-Pad24)") (class "Default")
      (node (ref "IC2") (pin "24") (pinfunction "PD4_24") (pintype "bidirectional"))
    )
    (net (code "107") (name "unconnected-(IC2-PD5-Pad25)") (class "Default")
      (node (ref "IC2") (pin "25") (pinfunction "PD5_25") (pintype "bidirectional"))
    )
    (net (code "108") (name "unconnected-(IC2-PD6-Pad26)") (class "Default")
      (node (ref "IC2") (pin "26") (pinfunction "PD6_26") (pintype "bidirectional"))
    )
    (net (code "109") (name "unconnected-(IC2-PD7-Pad27)") (class "Default")
      (node (ref "IC2") (pin "27") (pinfunction "PD7_27") (pintype "bidirectional"))
    )
    (net (code "110") (name "unconnected-(IC2-PDI_DATA-Pad34)") (class "Default")
      (node (ref "IC2") (pin "34") (pinfunction "PDI_DATA_34") (pintype "bidirectional"))
    )
    (net (code "111") (name "unconnected-(IC2-PE0-Pad28)") (class "Default")
      (node (ref "IC2") (pin "28") (pinfunction "PE0_28") (pintype "bidirectional"))
    )
    (net (code "112") (name "unconnected-(IC2-PE1-Pad29)") (class "Default")
      (node (ref "IC2") (pin "29") (pinfunction "PE1_29") (pintype "bidirectional"))
    )
    (net (code "113") (name "unconnected-(IC2-PE2-Pad32)") (class "Default")
      (node (ref "IC2") (pin "32") (pinfunction "PE2_32") (pintype "bidirectional"))
    )
    (net (code "114") (name "unconnected-(IC2-PE3-Pad33)") (class "Default")
      (node (ref "IC2") (pin "33") (pinfunction "PE3_33") (pintype "bidirectional"))
    )
    (net (code "115") (name "unconnected-(JP6-Pad2)") (class "Default")
      (node (ref "JP6") (pin "2") (pinfunction "2_2") (pintype "passive"))
    )
    (net (code "116") (name "unconnected-(JP6-Pad4)") (class "Default")
      (node (ref "JP6") (pin "4") (pinfunction "4_4") (pintype "passive"))
    )
    (net (code "117") (name "unconnected-(JP6-Pad12)") (class "Default")
      (node (ref "JP6") (pin "12") (pinfunction "12_12") (pintype "passive"))
    )
    (net (code "118") (name "unconnected-(JP7-Pad2)") (class "Default")
      (node (ref "JP7") (pin "2") (pinfunction "2_2") (pintype "passive"))
    )
    (net (code "119") (name "unconnected-(JP7-Pad4)") (class "Default")
      (node (ref "JP7") (pin "4") (pinfunction "4_4") (pintype "passive"))
    )
    (net (code "120") (name "unconnected-(JP7-Pad12)") (class "Default")
      (node (ref "JP7") (pin "12") (pinfunction "12_12") (pintype "passive"))
    )
    (net (code "121") (name "unconnected-(JP8-Pad2)") (class "Default")
      (node (ref "JP8") (pin "2") (pinfunction "2_2") (pintype "passive"))
    )
    (net (code "122") (name "unconnected-(JP8-Pad3)") (class "Default")
      (node (ref "JP8") (pin "3") (pinfunction "3_3") (pintype "passive"))
    )
    (net (code "123") (name "unconnected-(JP8-Pad4)") (class "Default")
      (node (ref "JP8") (pin "4") (pinfunction "4_4") (pintype "passive"))
    )
    (net (code "124") (name "unconnected-(U$2-(TRST)-Pad8)") (class "Default")
      (node (ref "U$2") (pin "8") (pinfunction "(TRST)_8") (pintype "bidirectional"))
    )
    (net (code "125") (name "unconnected-(U$13-PadID)") (class "Default")
      (node (ref "U$13") (pin "ID") (pinfunction "ID_ID") (pintype "bidirectional"))
    )
    (net (code "126") (name "unconnected-(U1-CBUS0-Pad18)") (class "Default")
      (node (ref "U1") (pin "18") (pinfunction "CBUS0_18") (pintype "bidirectional"))
    )
    (net (code "127") (name "unconnected-(U1-CBUS3-Pad19)") (class "Default")
      (node (ref "U1") (pin "19") (pinfunction "CBUS3_19") (pintype "bidirectional"))
    )
    (net (code "128") (name "unconnected-(U1-~{CTS}-Pad9)") (class "Default")
      (node (ref "U1") (pin "9") (pinfunction "~{CTS}_9") (pintype "bidirectional"))
    )
    (net (code "129") (name "unconnected-(U1-~{DCD}-Pad8)") (class "Default")
      (node (ref "U1") (pin "8") (pinfunction "~{DCD}_8") (pintype "bidirectional"))
    )
    (net (code "130") (name "unconnected-(U1-~{DSR}-Pad7)") (class "Default")
      (node (ref "U1") (pin "7") (pinfunction "~{DSR}_7") (pintype "bidirectional"))
    )
    (net (code "131") (name "unconnected-(U1-~{RI}-Pad5)") (class "Default")
      (node (ref "U1") (pin "5") (pinfunction "~{RI}_5") (pintype "bidirectional"))
    )
    (net (code "132") (name "unconnected-(U1-~{RTS}-Pad2)") (class "Default")
      (node (ref "U1") (pin "2") (pinfunction "~{RTS}_2") (pintype "bidirectional"))
    )
  )
)
